# 5V_Supply.net
KiCad netlist of a schematic drawn in Altium Designer
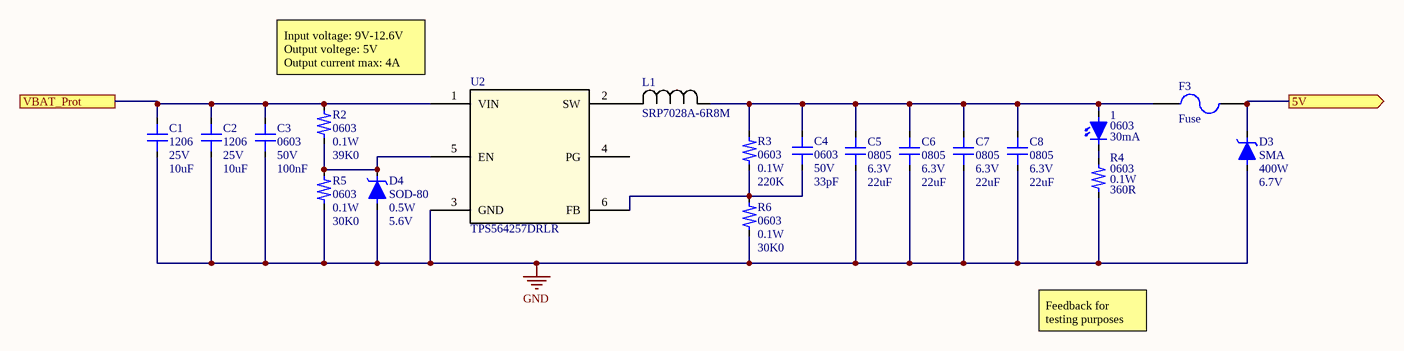
[diagram p0: 5V_Supply.SchDoc]

(export (version "E")
  (design (tool "Eeschema 10.0.6"))
  (components
    (comp (ref "1")
      (value "0603")
      (footprint "LED_0603")
      (fields
        (field (name "PART NUMBER") "FYLS-0603UGC")
        (field (name "TOLERANCE") "5%")
        (field (name "RATING") "30mA")
      )
      (libsource (lib "Components") (part "Diode_LED"))
    )
    (comp (ref "C1")
      (value "1206")
      (footprint "C_1206")
      (fields
        (field (name "TOLERANCE") "10%")
        (field (name "PART NUMBER") "C3216X7R1E106K160AB")
        (field (name "RATING") "25V")
        (field (name "ALTIUM_VALUE") "10uF")
      )
      (libsource (lib "Components") (part "Capacitor_Chip"))
    )
    (comp (ref "C2")
      (value "1206")
      (footprint "C_1206")
      (fields
        (field (name "TOLERANCE") "10%")
        (field (name "PART NUMBER") "C3216X7R1E106K160AB")
        (field (name "RATING") "25V")
        (field (name "ALTIUM_VALUE") "10uF")
      )
      (libsource (lib "Components") (part "Capacitor_Chip"))
    )
    (comp (ref "C3")
      (value "0603")
      (footprint "C_0603")
      (fields
        (field (name "TOLERANCE") "10%")
        (field (name "PART NUMBER") "CC0603KRX7R9BB104")
        (field (name "RATING") "50V")
        (field (name "ALTIUM_VALUE") "100nF")
        (field (name "NI PART NUMBER") "716340-01")
      )
      (libsource (lib "Components") (part "Capacitor_Chip"))
    )
    (comp (ref "C4")
      (value "0603")
      (footprint "C_0603")
      (fields
        (field (name "TOLERANCE") "5%")
        (field (name "PART NUMBER") "CL10C330JB8NNNC")
        (field (name "RATING") "50V")
        (field (name "ALTIUM_VALUE") "33pF")
        (field (name "NI PART NUMBER") "715511-01")
      )
      (libsource (lib "Components") (part "Capacitor_Chip"))
    )
    (comp (ref "C5")
      (value "0805")
      (footprint "C_0805")
      (fields
        (field (name "TOLERANCE") "20%")
        (field (name "PART NUMBER") "CL21A226MQQNNNG")
        (field (name "RATING") "6.3V")
        (field (name "ALTIUM_VALUE") "22uF")
      )
      (libsource (lib "Components") (part "Capacitor_Chip"))
    )
    (comp (ref "C6")
      (value "0805")
      (footprint "C_0805")
      (fields
        (field (name "TOLERANCE") "20%")
        (field (name "PART NUMBER") "CL21A226MQQNNNG")
        (field (name "RATING") "6.3V")
        (field (name "ALTIUM_VALUE") "22uF")
      )
      (libsource (lib "Components") (part "Capacitor_Chip"))
    )
    (comp (ref "C7")
      (value "0805")
      (footprint "C_0805")
      (fields
        (field (name "TOLERANCE") "20%")
        (field (name "PART NUMBER") "CL21A226MQQNNNG")
        (field (name "RATING") "6.3V")
        (field (name "ALTIUM_VALUE") "22uF")
      )
      (libsource (lib "Components") (part "Capacitor_Chip"))
    )
    (comp (ref "C8")
      (value "0805")
      (footprint "C_0805")
      (fields
        (field (name "TOLERANCE") "20%")
        (field (name "PART NUMBER") "CL21A226MQQNNNG")
        (field (name "RATING") "6.3V")
        (field (name "ALTIUM_VALUE") "22uF")
      )
      (libsource (lib "Components") (part "Capacitor_Chip"))
    )
    (comp (ref "D3")
      (value "SMA")
      (footprint "SMA")
      (fields
        (field (name "PART NUMBER") "SMAJ5.0A")
        (field (name "TOLERANCE") "5%")
        (field (name "RATING") "400W")
        (field (name "ALTIUM_VALUE") "6.7V")
      )
      (libsource (lib "Components") (part "Diode_Transient_Sup"))
    )
    (comp (ref "D4")
      (value "SOD-80")
      (footprint "SOD-80")
      (fields
        (field (name "PART NUMBER") "BZV55C5V6")
        (field (name "RATING") "0.5W")
        (field (name "ALTIUM_VALUE") "5.6V")
      )
      (libsource (lib "Components") (part "Diode_Zener"))
    )
    (comp (ref "F3")
      (value "Fuse")
      (footprint "F_2410")
      (fields (field (name "PART NUMBER") "0451003.MRL"))
      (libsource (lib "Components") (part "Fuse"))
    )
    (comp (ref "L1")
      (value "SRP7028A-6R8M")
      (footprint "IND_SRP7028A-6R8M_BRN")
      (description "No Description Available")
      (fields (field (name "COPYRIGHT") "Copyright (C) 2023 Ultra Librarian. All rights reserved."))
      (libsource (lib "SRP7028A-6R8M") (part "SRP7028A-6R8M"))
    )
    (comp (ref "R2")
      (value "0603")
      (footprint "R_0603")
      (fields
        (field (name "TOLERANCE") "5%")
        (field (name "PART NUMBER") "CR-03JL7---39K")
        (field (name "RATING") "0.1W")
        (field (name "ALTIUM_VALUE") "39K0")
        (field (name "NI PART NUMBER") "613245-01")
      )
      (libsource (lib "Components") (part "Resistor_Chip"))
    )
    (comp (ref "R3")
      (value "0603")
      (footprint "R_0603")
      (fields
        (field (name "TOLERANCE") "1%")
        (field (name "PART NUMBER") "CR-03FL7--220K")
        (field (name "RATING") "0.1W")
        (field (name "ALTIUM_VALUE") "220K")
        (field (name "NI PART NUMBER") "612705-01")
      )
      (libsource (lib "") (part "Resistor_Chip_1"))
    )
    (comp (ref "R4")
      (value "0603")
      (footprint "R_0603")
      (fields
        (field (name "TOLERANCE") "1%")
        (field (name "PART NUMBER") "CR-03FL7--360R")
        (field (name "RATING") "0.1W")
        (field (name "ALTIUM_VALUE") "360R")
      )
      (libsource (lib "Components") (part "Resistor_Chip"))
    )
    (comp (ref "R5")
      (value "0603")
      (footprint "R_0603")
      (fields
        (field (name "TOLERANCE") "1%")
        (field (name "PART NUMBER") "CR-03FL7---30K")
        (field (name "RATING") "0.1W")
        (field (name "ALTIUM_VALUE") "30K0")
        (field (name "NI PART NUMBER") "612699-01")
      )
      (libsource (lib "Components") (part "Resistor_Chip"))
    )
    (comp (ref "R6")
      (value "0603")
      (footprint "R_0603")
      (fields
        (field (name "TOLERANCE") "1%")
        (field (name "PART NUMBER") "CR-03FL7---30K")
        (field (name "RATING") "0.1W")
        (field (name "ALTIUM_VALUE") "30K0")
        (field (name "NI PART NUMBER") "612699-01")
      )
      (libsource (lib "Components") (part "Resistor_Chip"))
    )
    (comp (ref "U2")
      (value "TPS564257DRLR")
      (footprint "TPS564242DRLR_TEX")
      (description "No Description Available")
      (fields (field (name "COPYRIGHT") "Copyright (C) 2023 Ultra Librarian. All rights reserved."))
      (libsource (lib "TPS564257DRLR") (part "TPS564257DRLR"))
    )
  )
  (nets
    (net (code "1") (name "/5V") (class "Default")
      (node (ref "D3") (pin "1") (pinfunction "DC_1") (pintype "passive"))
      (node (ref "F3") (pin "2") (pinfunction "2_2") (pintype "passive"))
    )
    (net (code "2") (name "/VBAT_Prot") (class "Default")
      (node (ref "C1") (pin "2") (pinfunction "C2_2") (pintype "passive"))
      (node (ref "C2") (pin "2") (pinfunction "C2_2") (pintype "passive"))
      (node (ref "C3") (pin "2") (pinfunction "C2_2") (pintype "passive"))
      (node (ref "R2") (pin "2") (pinfunction "R2_2") (pintype "passive"))
      (node (ref "U2") (pin "1") (pinfunction "VIN_1") (pintype "power_in"))
    )
    (net (code "3") (name "GND") (class "Default")
      (node (ref "C1") (pin "1") (pinfunction "C1_1") (pintype "passive"))
      (node (ref "C2") (pin "1") (pinfunction "C1_1") (pintype "passive"))
      (node (ref "C3") (pin "1") (pinfunction "C1_1") (pintype "passive"))
      (node (ref "C5") (pin "1") (pinfunction "C1_1") (pintype "passive"))
      (node (ref "C6") (pin "1") (pinfunction "C1_1") (pintype "passive"))
      (node (ref "C7") (pin "1") (pinfunction "C1_1") (pintype "passive"))
      (node (ref "C8") (pin "1") (pinfunction "C1_1") (pintype "passive"))
      (node (ref "D3") (pin "2") (pinfunction "DA_2") (pintype "passive"))
      (node (ref "D4") (pin "2") (pinfunction "DA_2") (pintype "passive"))
      (node (ref "R4") (pin "1") (pinfunction "R1_1") (pintype "passive"))
      (node (ref "R5") (pin "1") (pinfunction "R1_1") (pintype "passive"))
      (node (ref "R6") (pin "1") (pinfunction "R1_1") (pintype "passive"))
      (node (ref "U2") (pin "3") (pinfunction "GND_3") (pintype "power_in"))
    )
    (net (code "4") (name "Net-(1-DA)") (class "Default")
      (node (ref "1") (pin "2") (pinfunction "DA_2") (pintype "passive"))
      (node (ref "C4") (pin "2") (pinfunction "C2_2") (pintype "passive"))
      (node (ref "C5") (pin "2") (pinfunction "C2_2") (pintype "passive"))
      (node (ref "C6") (pin "2") (pinfunction "C2_2") (pintype "passive"))
      (node (ref "C7") (pin "2") (pinfunction "C2_2") (pintype "passive"))
      (node (ref "C8") (pin "2") (pinfunction "C2_2") (pintype "passive"))
      (node (ref "F3") (pin "1") (pinfunction "1_1") (pintype "passive"))
      (node (ref "L1") (pin "1") (pinfunction "1_1") (pintype "passive"))
      (node (ref "R3") (pin "1") (pinfunction "R1_1") (pintype "passive"))
    )
    (net (code "5") (name "Net-(1-DC)") (class "Default")
      (node (ref "1") (pin "1") (pinfunction "DC_1") (pintype "passive"))
      (node (ref "R4") (pin "2") (pinfunction "R2_2") (pintype "passive"))
    )
    (net (code "6") (name "Net-(C4-C1)") (class "Default")
      (node (ref "C4") (pin "1") (pinfunction "C1_1") (pintype "passive"))
      (node (ref "R3") (pin "2") (pinfunction "R2_2") (pintype "passive"))
      (node (ref "R6") (pin "2") (pinfunction "R2_2") (pintype "passive"))
      (node (ref "U2") (pin "6") (pinfunction "FB_6") (pintype "passive"))
    )
    (net (code "7") (name "Net-(D4-DC)") (class "Default")
      (node (ref "D4") (pin "1") (pinfunction "DC_1") (pintype "passive"))
      (node (ref "R2") (pin "1") (pinfunction "R1_1") (pintype "passive"))
      (node (ref "R5") (pin "2") (pinfunction "R2_2") (pintype "passive"))
      (node (ref "U2") (pin "5") (pinfunction "EN_5") (pintype "passive"))
    )
    (net (code "8") (name "Net-(U2-SW)") (class "Default")
      (node (ref "L1") (pin "2") (pinfunction "2_2") (pintype "passive"))
      (node (ref "U2") (pin "2") (pinfunction "SW_2") (pintype "power_in"))
    )
    (net (code "9") (name "unconnected-(U2-PG-Pad4)") (class "Default")
      (node (ref "U2") (pin "4") (pinfunction "PG_4") (pintype "passive"))
    )
  )
)
